# tm-motor-driver.net
KiCad netlist of a schematic drawn in EAGLE
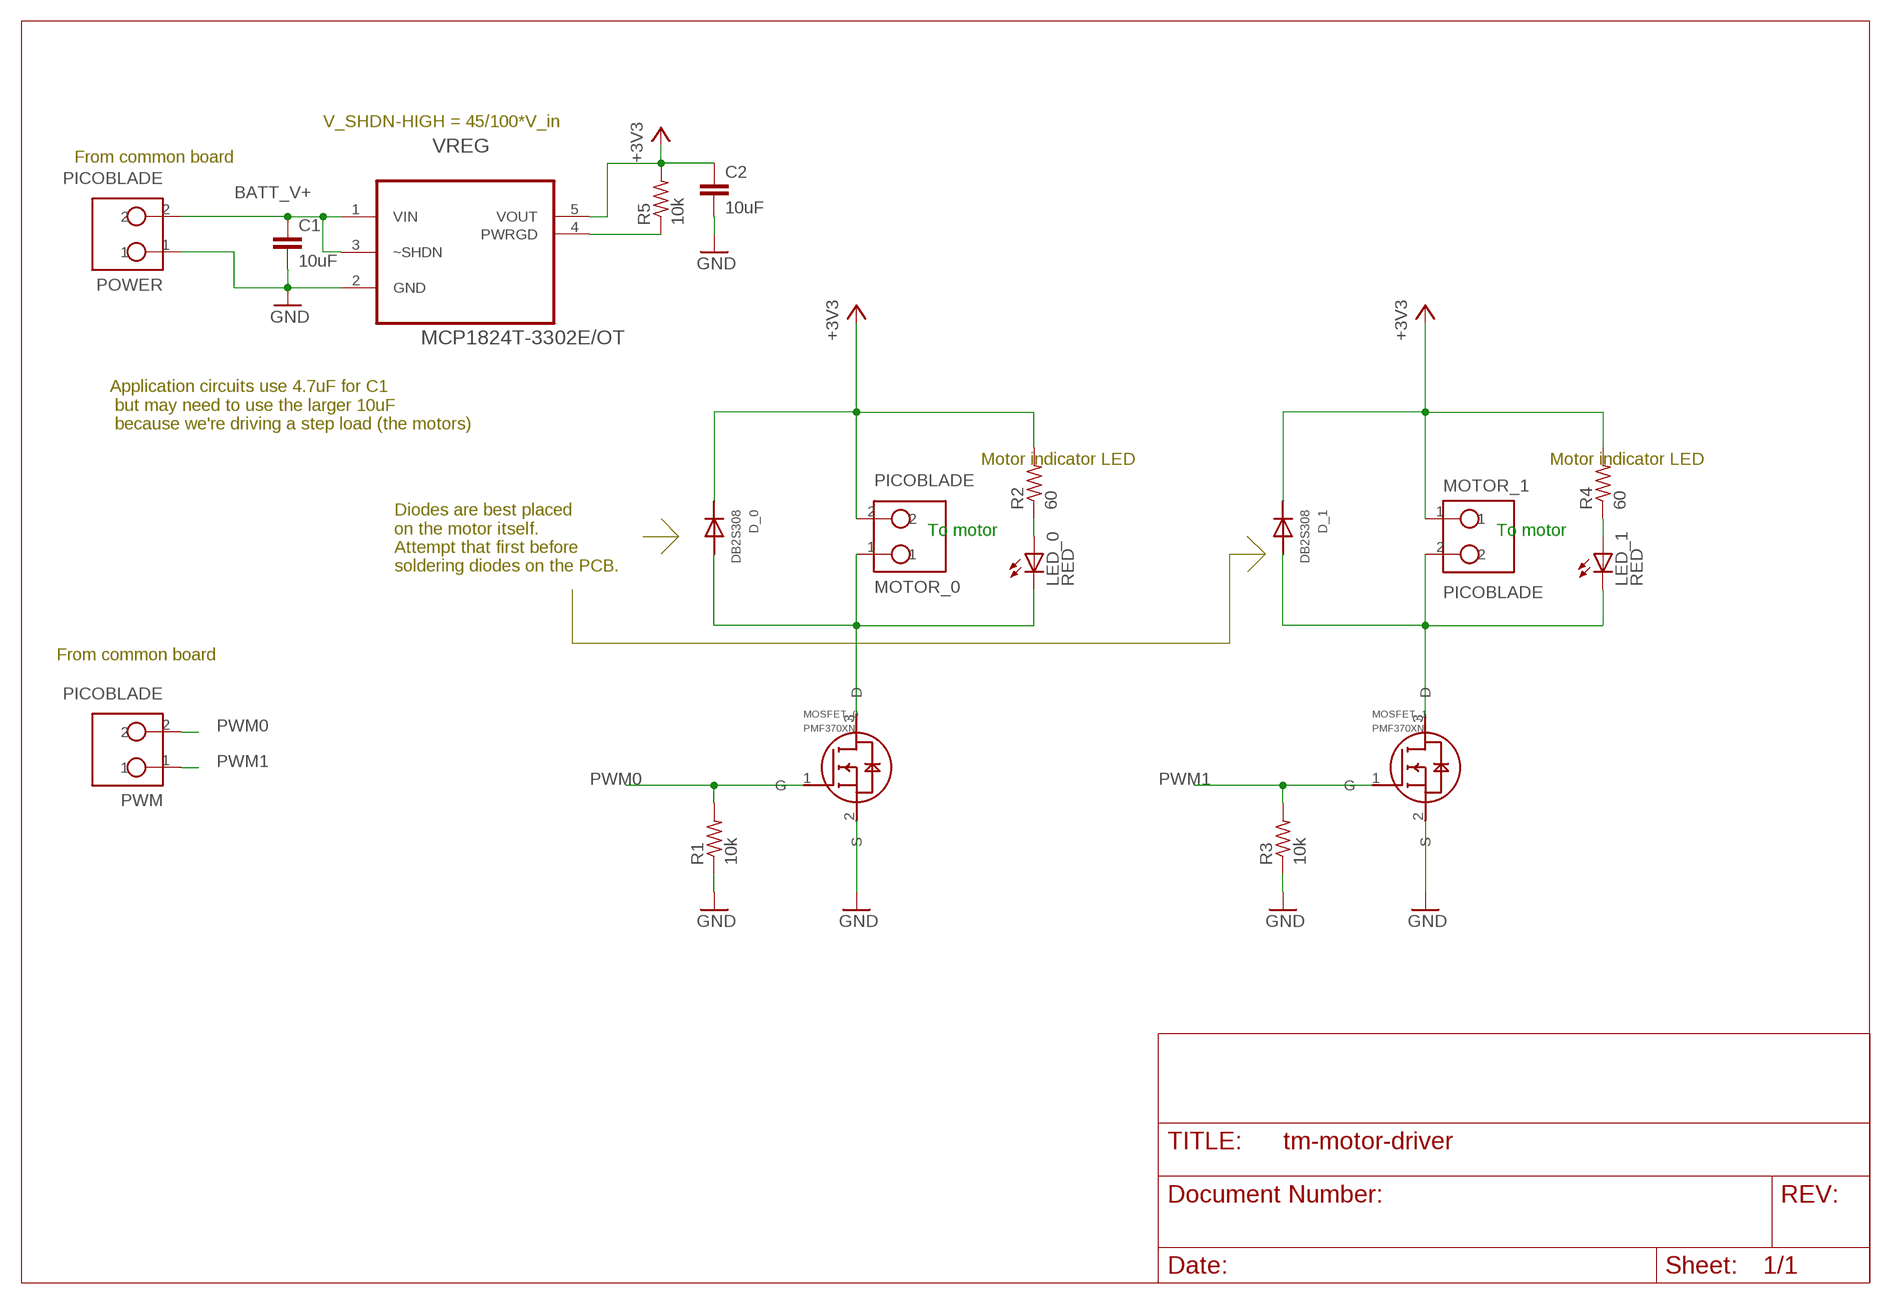
[diagram p0: schematic, sheet 1]

(export (version "E")
  (design (tool "Eeschema 10.0.6"))
  (components
    (comp (ref "C1")
      (value "10uF")
      (footprint "eagle-import:C0805")
      (libsource (lib "eagle-import") (part "C-EUC0805"))
    )
    (comp (ref "C2")
      (value "10uF")
      (footprint "eagle-import:C0805")
      (libsource (lib "eagle-import") (part "C-EUC0805"))
    )
    (comp (ref "D_0")
      (value "DB2S308")
      (footprint "eagle-import:SOD-523")
      (libsource (lib "eagle-import") (part "DB2S308"))
    )
    (comp (ref "D_1")
      (value "DB2S308")
      (footprint "eagle-import:SOD-523")
      (libsource (lib "eagle-import") (part "DB2S308"))
    )
    (comp (ref "LED_0")
      (value "RED")
      (footprint "eagle-import:CHIPLED_0805")
      (libsource (lib "eagle-import") (part "LEDCHIPLED_0805"))
    )
    (comp (ref "LED_1")
      (value "RED")
      (footprint "eagle-import:CHIPLED_0805")
      (libsource (lib "eagle-import") (part "LEDCHIPLED_0805"))
    )
    (comp (ref "MOSFET_0")
      (value "PMF370XN")
      (footprint "eagle-import:SOT323(SC-70)")
      (libsource (lib "eagle-import") (part "PMF370XN"))
    )
    (comp (ref "MOSFET_1")
      (value "PMF370XN")
      (footprint "eagle-import:SOT323(SC-70)")
      (libsource (lib "eagle-import") (part "PMF370XN"))
    )
    (comp (ref "MOTOR_0")
      (value "PICOBLADE")
      (footprint "eagle-import:PICOBLADE")
      (libsource (lib "eagle-import") (part "PICOBLADE"))
    )
    (comp (ref "MOTOR_1")
      (value "PICOBLADE")
      (footprint "eagle-import:PICOBLADE")
      (libsource (lib "eagle-import") (part "PICOBLADE"))
    )
    (comp (ref "POWER")
      (value "PICOBLADE")
      (footprint "eagle-import:PICOBLADE")
      (libsource (lib "eagle-import") (part "PICOBLADE"))
    )
    (comp (ref "PWM")
      (value "PICOBLADE")
      (footprint "eagle-import:PICOBLADE")
      (libsource (lib "eagle-import") (part "PICOBLADE"))
    )
    (comp (ref "R1")
      (value "10k")
      (footprint "eagle-import:R0805")
      (libsource (lib "eagle-import") (part "R-US_R0805"))
    )
    (comp (ref "R2")
      (value "60")
      (footprint "eagle-import:R0805")
      (libsource (lib "eagle-import") (part "R-US_R0805"))
    )
    (comp (ref "R3")
      (value "10k")
      (footprint "eagle-import:R0805")
      (libsource (lib "eagle-import") (part "R-US_R0805"))
    )
    (comp (ref "R4")
      (value "60")
      (footprint "eagle-import:R0805")
      (libsource (lib "eagle-import") (part "R-US_R0805"))
    )
    (comp (ref "R5")
      (value "10k")
      (footprint "eagle-import:R0805")
      (libsource (lib "eagle-import") (part "R-US_R0805"))
    )
    (comp (ref "VREG")
      (value "MCP1824T-3302E/OT")
      (footprint "eagle-import:SOT95P270X145-5N")
      (libsource (lib "eagle-import") (part "MCP1824T-3302E/OT"))
    )
  )
  (nets
    (net (code "1") (name "+3V3") (class "Default")
      (node (ref "C2") (pin "1") (pinfunction "1_1") (pintype "passive"))
      (node (ref "D_0") (pin "1") (pinfunction "CATHODE_1") (pintype "bidirectional"))
      (node (ref "D_1") (pin "1") (pinfunction "CATHODE_1") (pintype "bidirectional"))
      (node (ref "MOTOR_0") (pin "2") (pinfunction "2_2") (pintype "bidirectional"))
      (node (ref "MOTOR_1") (pin "1") (pinfunction "1_1") (pintype "bidirectional"))
      (node (ref "R2") (pin "2") (pinfunction "2_2") (pintype "passive"))
      (node (ref "R4") (pin "2") (pinfunction "2_2") (pintype "passive"))
      (node (ref "R5") (pin "2") (pinfunction "2_2") (pintype "passive"))
      (node (ref "VREG") (pin "5") (pinfunction "VOUT_5") (pintype "power_in"))
    )
    (net (code "2") (name "/BATT_V+") (class "Default")
      (node (ref "C1") (pin "1") (pinfunction "1_1") (pintype "passive"))
      (node (ref "POWER") (pin "2") (pinfunction "2_2") (pintype "bidirectional"))
      (node (ref "VREG") (pin "1") (pinfunction "VIN_1") (pintype "power_in"))
      (node (ref "VREG") (pin "3") (pinfunction "~{SHDN}_3") (pintype "input"))
    )
    (net (code "3") (name "/PWM0") (class "Default")
      (node (ref "MOSFET_0") (pin "1") (pinfunction "G_1") (pintype "bidirectional"))
      (node (ref "PWM") (pin "2") (pinfunction "2_2") (pintype "bidirectional"))
      (node (ref "R1") (pin "2") (pinfunction "2_2") (pintype "passive"))
    )
    (net (code "4") (name "/PWM1") (class "Default")
      (node (ref "MOSFET_1") (pin "1") (pinfunction "G_1") (pintype "bidirectional"))
      (node (ref "PWM") (pin "1") (pinfunction "1_1") (pintype "bidirectional"))
      (node (ref "R3") (pin "2") (pinfunction "2_2") (pintype "passive"))
    )
    (net (code "5") (name "GND") (class "Default")
      (node (ref "C1") (pin "2") (pinfunction "2_2") (pintype "passive"))
      (node (ref "C2") (pin "2") (pinfunction "2_2") (pintype "passive"))
      (node (ref "MOSFET_0") (pin "2") (pinfunction "S_2") (pintype "bidirectional"))
      (node (ref "MOSFET_1") (pin "2") (pinfunction "S_2") (pintype "bidirectional"))
      (node (ref "POWER") (pin "1") (pinfunction "1_1") (pintype "bidirectional"))
      (node (ref "R1") (pin "1") (pinfunction "1_1") (pintype "passive"))
      (node (ref "R3") (pin "1") (pinfunction "1_1") (pintype "passive"))
      (node (ref "VREG") (pin "2") (pinfunction "GND_2") (pintype "power_in"))
    )
    (net (code "6") (name "Net-(D_0-ANODE)") (class "Default")
      (node (ref "D_0") (pin "2") (pinfunction "ANODE_2") (pintype "bidirectional"))
      (node (ref "LED_0") (pin "C") (pinfunction "C_C") (pintype "passive"))
      (node (ref "MOSFET_0") (pin "3") (pinfunction "D_3") (pintype "bidirectional"))
      (node (ref "MOTOR_0") (pin "1") (pinfunction "1_1") (pintype "bidirectional"))
    )
    (net (code "7") (name "Net-(D_1-ANODE)") (class "Default")
      (node (ref "D_1") (pin "2") (pinfunction "ANODE_2") (pintype "bidirectional"))
      (node (ref "LED_1") (pin "C") (pinfunction "C_C") (pintype "passive"))
      (node (ref "MOSFET_1") (pin "3") (pinfunction "D_3") (pintype "bidirectional"))
      (node (ref "MOTOR_1") (pin "2") (pinfunction "2_2") (pintype "bidirectional"))
    )
    (net (code "8") (name "Net-(LED_0-PadA)") (class "Default")
      (node (ref "LED_0") (pin "A") (pinfunction "A_A") (pintype "passive"))
      (node (ref "R2") (pin "1") (pinfunction "1_1") (pintype "passive"))
    )
    (net (code "9") (name "Net-(LED_1-PadA)") (class "Default")
      (node (ref "LED_1") (pin "A") (pinfunction "A_A") (pintype "passive"))
      (node (ref "R4") (pin "1") (pinfunction "1_1") (pintype "passive"))
    )
    (net (code "10") (name "Net-(VREG-PWRGD)") (class "Default")
      (node (ref "R5") (pin "1") (pinfunction "1_1") (pintype "passive"))
      (node (ref "VREG") (pin "4") (pinfunction "PWRGD_4") (pintype "output"))
    )
  )
)
